# Conexiones_tablero.net
KiCad netlist of a schematic drawn in EAGLE
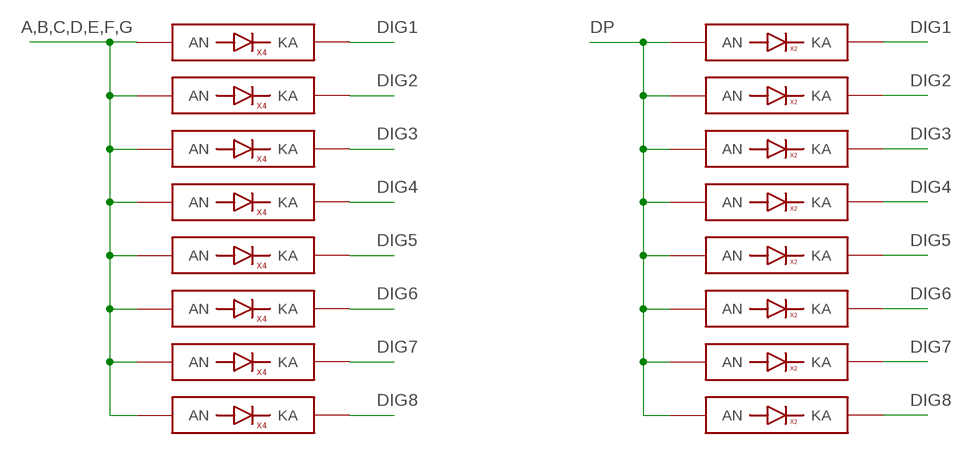
[diagram p0: schematic, sheet 1]

(export (version "E")
  (design (tool "Eeschema 10.0.6"))
  (components
    (comp (ref "U$1") (value "4") (footprint "eagle-import:AA") (libsource (lib "eagle-import") (part "4")))
    (comp (ref "U$2") (value "2") (footprint "eagle-import:AA") (libsource (lib "eagle-import") (part "2")))
    (comp (ref "U$3") (value "4") (footprint "eagle-import:AA") (libsource (lib "eagle-import") (part "4")))
    (comp (ref "U$4") (value "4") (footprint "eagle-import:AA") (libsource (lib "eagle-import") (part "4")))
    (comp (ref "U$5") (value "4") (footprint "eagle-import:AA") (libsource (lib "eagle-import") (part "4")))
    (comp (ref "U$6") (value "2") (footprint "eagle-import:AA") (libsource (lib "eagle-import") (part "2")))
    (comp (ref "U$7") (value "4") (footprint "eagle-import:AA") (libsource (lib "eagle-import") (part "4")))
    (comp (ref "U$8") (value "4") (footprint "eagle-import:AA") (libsource (lib "eagle-import") (part "4")))
    (comp (ref "U$9") (value "4") (footprint "eagle-import:AA") (libsource (lib "eagle-import") (part "4")))
    (comp (ref "U$10") (value "4") (footprint "eagle-import:AA") (libsource (lib "eagle-import") (part "4")))
    (comp (ref "U$11") (value "2") (footprint "eagle-import:AA") (libsource (lib "eagle-import") (part "2")))
    (comp (ref "U$12") (value "2") (footprint "eagle-import:AA") (libsource (lib "eagle-import") (part "2")))
    (comp (ref "U$13") (value "2") (footprint "eagle-import:AA") (libsource (lib "eagle-import") (part "2")))
    (comp (ref "U$14") (value "2") (footprint "eagle-import:AA") (libsource (lib "eagle-import") (part "2")))
    (comp (ref "U$15") (value "2") (footprint "eagle-import:AA") (libsource (lib "eagle-import") (part "2")))
    (comp (ref "U$16") (value "2") (footprint "eagle-import:AA") (libsource (lib "eagle-import") (part "2")))
  )
  (nets
    (net (code "1") (name "/A,B,C,D,E,F,G") (class "Default")
      (node (ref "U$1") (pin "P$1") (pinfunction "AN_P$1") (pintype "bidirectional"))
      (node (ref "U$10") (pin "P$1") (pinfunction "AN_P$1") (pintype "bidirectional"))
      (node (ref "U$3") (pin "P$1") (pinfunction "AN_P$1") (pintype "bidirectional"))
      (node (ref "U$4") (pin "P$1") (pinfunction "AN_P$1") (pintype "bidirectional"))
      (node (ref "U$5") (pin "P$1") (pinfunction "AN_P$1") (pintype "bidirectional"))
      (node (ref "U$7") (pin "P$1") (pinfunction "AN_P$1") (pintype "bidirectional"))
      (node (ref "U$8") (pin "P$1") (pinfunction "AN_P$1") (pintype "bidirectional"))
      (node (ref "U$9") (pin "P$1") (pinfunction "AN_P$1") (pintype "bidirectional"))
    )
    (net (code "2") (name "/DIG1") (class "Default")
      (node (ref "U$10") (pin "P$2") (pinfunction "KA_P$2") (pintype "bidirectional"))
      (node (ref "U$2") (pin "P$2") (pinfunction "KA_P$2") (pintype "bidirectional"))
    )
    (net (code "3") (name "/DIG2") (class "Default")
      (node (ref "U$6") (pin "P$2") (pinfunction "KA_P$2") (pintype "bidirectional"))
      (node (ref "U$9") (pin "P$2") (pinfunction "KA_P$2") (pintype "bidirectional"))
    )
    (net (code "4") (name "/DIG3") (class "Default")
      (node (ref "U$11") (pin "P$2") (pinfunction "KA_P$2") (pintype "bidirectional"))
      (node (ref "U$7") (pin "P$2") (pinfunction "KA_P$2") (pintype "bidirectional"))
    )
    (net (code "5") (name "/DIG4") (class "Default")
      (node (ref "U$12") (pin "P$2") (pinfunction "KA_P$2") (pintype "bidirectional"))
      (node (ref "U$5") (pin "P$2") (pinfunction "KA_P$2") (pintype "bidirectional"))
    )
    (net (code "6") (name "/DIG5") (class "Default")
      (node (ref "U$13") (pin "P$2") (pinfunction "KA_P$2") (pintype "bidirectional"))
      (node (ref "U$8") (pin "P$2") (pinfunction "KA_P$2") (pintype "bidirectional"))
    )
    (net (code "7") (name "/DIG6") (class "Default")
      (node (ref "U$14") (pin "P$2") (pinfunction "KA_P$2") (pintype "bidirectional"))
      (node (ref "U$4") (pin "P$2") (pinfunction "KA_P$2") (pintype "bidirectional"))
    )
    (net (code "8") (name "/DIG7") (class "Default")
      (node (ref "U$15") (pin "P$2") (pinfunction "KA_P$2") (pintype "bidirectional"))
      (node (ref "U$3") (pin "P$2") (pinfunction "KA_P$2") (pintype "bidirectional"))
    )
    (net (code "9") (name "/DIG8") (class "Default")
      (node (ref "U$1") (pin "P$2") (pinfunction "KA_P$2") (pintype "bidirectional"))
      (node (ref "U$16") (pin "P$2") (pinfunction "KA_P$2") (pintype "bidirectional"))
    )
    (net (code "10") (name "/DP") (class "Default")
      (node (ref "U$11") (pin "P$1") (pinfunction "AN_P$1") (pintype "bidirectional"))
      (node (ref "U$12") (pin "P$1") (pinfunction "AN_P$1") (pintype "bidirectional"))
      (node (ref "U$13") (pin "P$1") (pinfunction "AN_P$1") (pintype "bidirectional"))
      (node (ref "U$14") (pin "P$1") (pinfunction "AN_P$1") (pintype "bidirectional"))
      (node (ref "U$15") (pin "P$1") (pinfunction "AN_P$1") (pintype "bidirectional"))
      (node (ref "U$16") (pin "P$1") (pinfunction "AN_P$1") (pintype "bidirectional"))
      (node (ref "U$2") (pin "P$1") (pinfunction "AN_P$1") (pintype "bidirectional"))
      (node (ref "U$6") (pin "P$1") (pinfunction "AN_P$1") (pintype "bidirectional"))
    )
  )
)
